# DIOT_CONN.net
KiCad netlist of a schematic drawn in Altium Designer
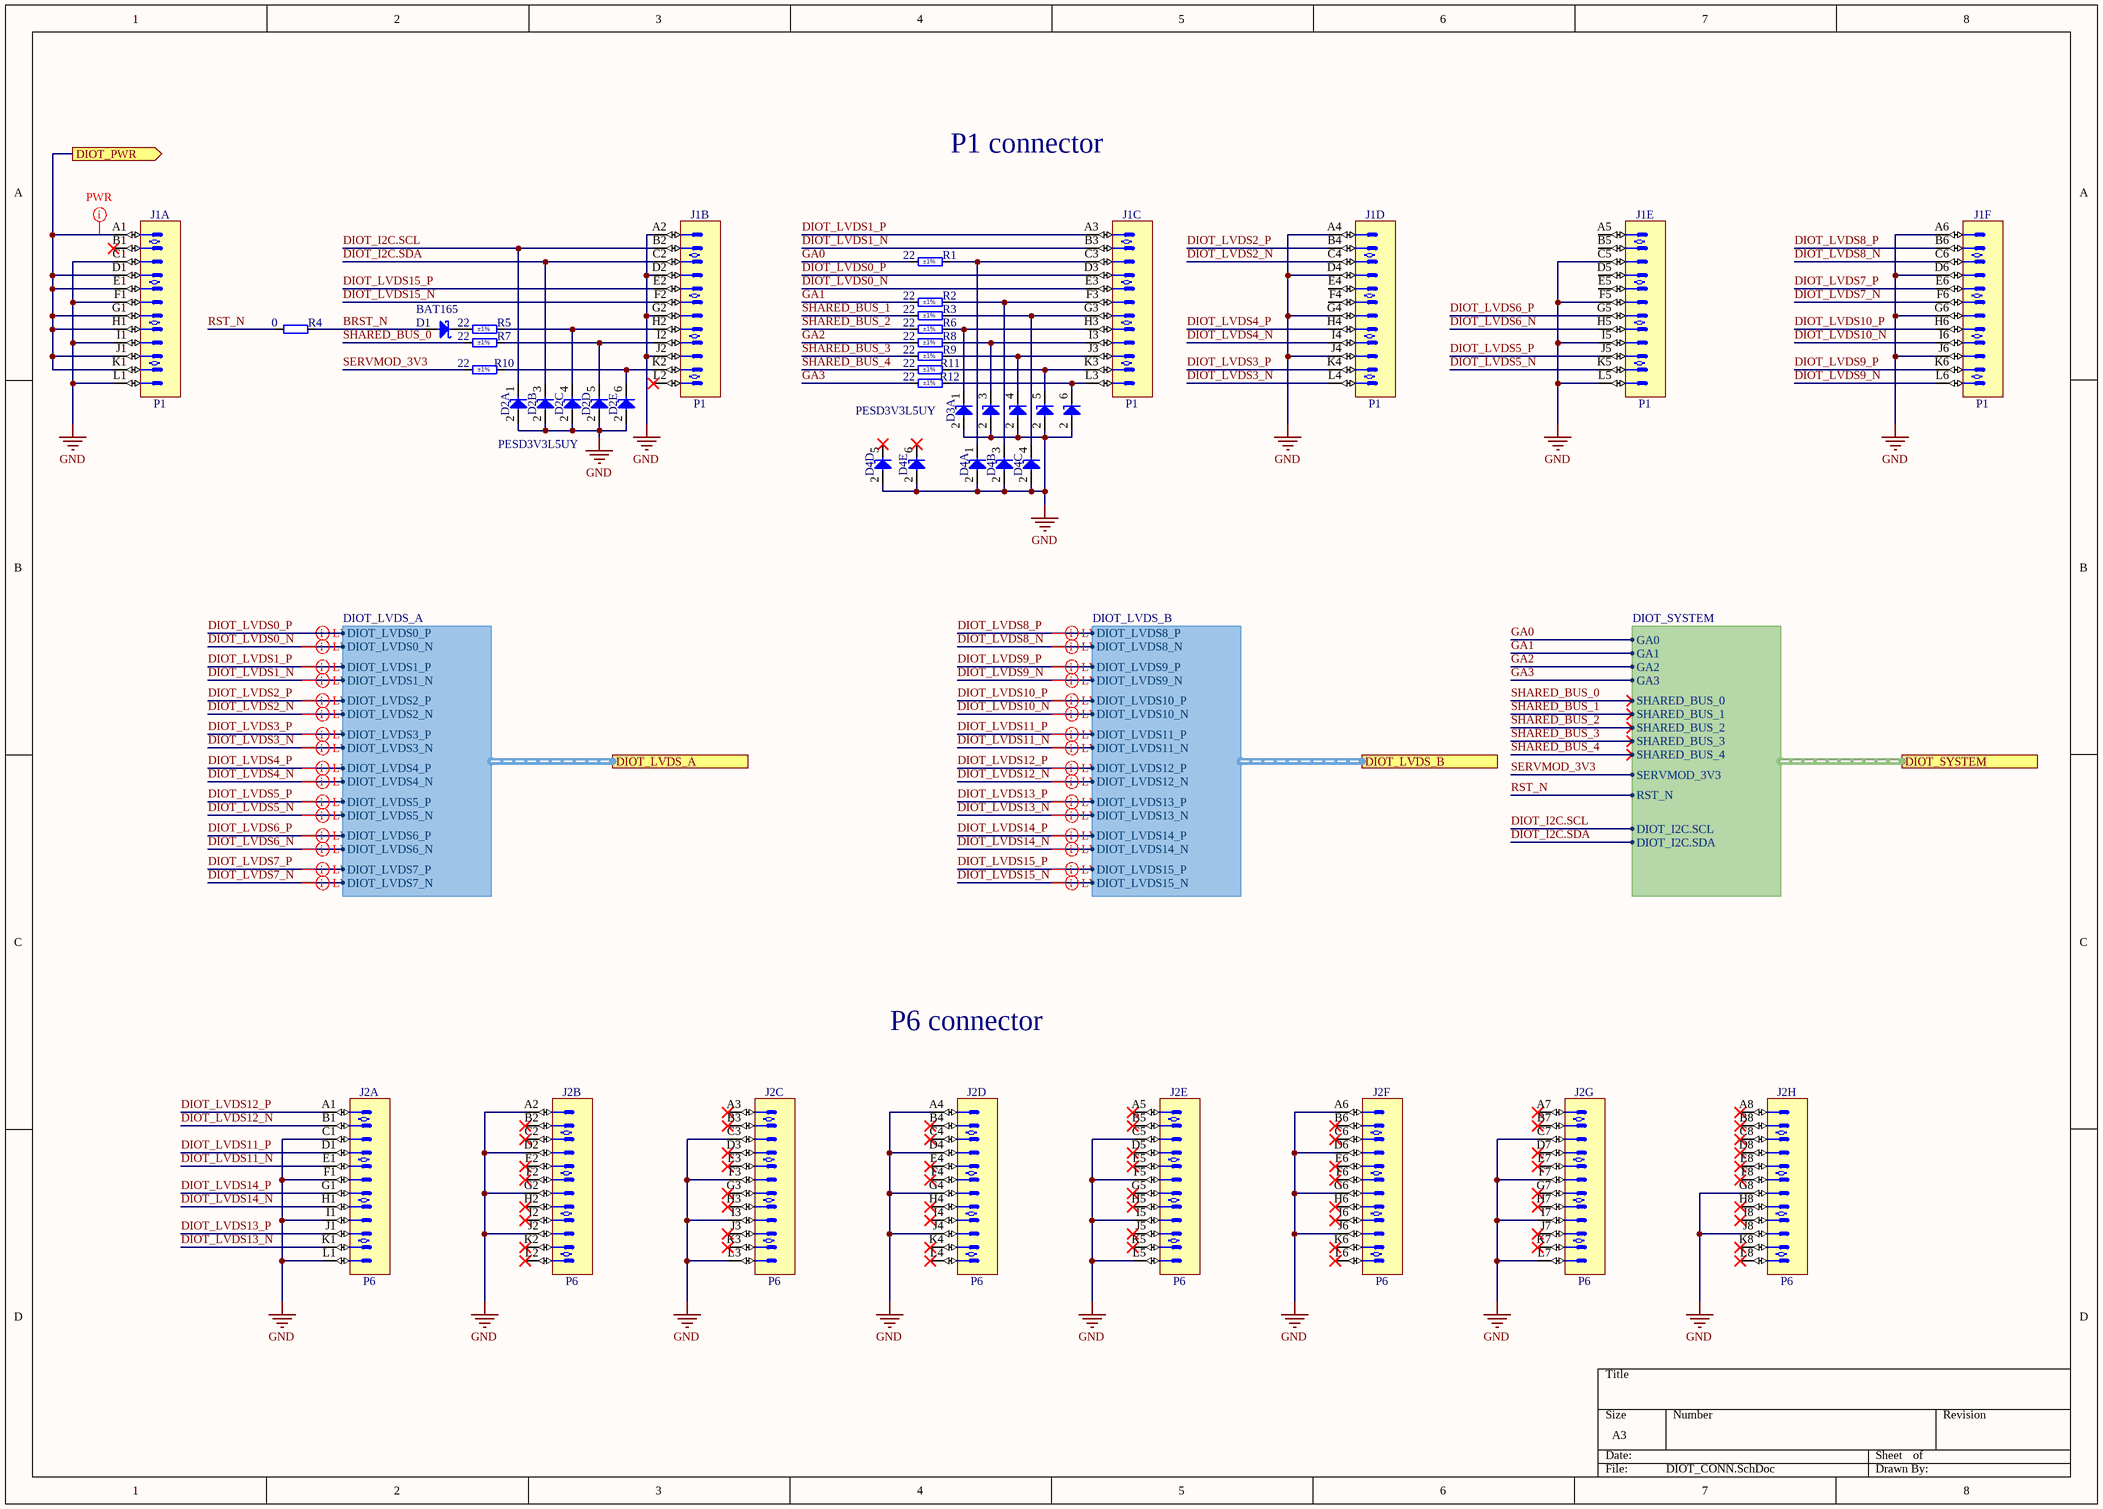
[diagram p0: DIOT_CONN.SchDoc]

(export (version "E")
  (design (tool "Eeschema 10.0.6"))
  (components
    (comp (ref "D1")
      (value "BAT165")
      (footprint "SOD2512X110N")
      (description "Schottky Diode")
      (fields
        (field (name "VOLTAGE") "40V")
        (field (name "POWER") "750mA")
        (field (name "AUTHOR") "CERN DEM JLC")
      )
      (libsource (lib "ICs And Semiconductors") (part "Diode Schottky"))
    )
    (comp (ref "D2")
      (value "PESD3V3L5UY")
      (footprint "SOT65P210X110-6N")
      (description "Fivefold ESD Protection Diode Arrays")
      (fields
        (field (name "VOLTAGE") "3.3V")
        (field (name "POWER") "200W")
        (field (name "AUTHOR") "CERN DEM WB")
      )
      (libsource (lib "ICs And Semiconductors") (part "PESD Array 5diodes 6pins Common anode2"))
    )
    (comp (ref "D3")
      (value "PESD3V3L5UY")
      (footprint "SOT65P210X110-6N")
      (description "Fivefold ESD Protection Diode Arrays")
      (fields
        (field (name "VOLTAGE") "3.3V")
        (field (name "POWER") "200W")
        (field (name "AUTHOR") "CERN DEM WB")
      )
      (libsource (lib "ICs And Semiconductors") (part "PESD Array 5diodes 6pins Common anode2"))
    )
    (comp (ref "D4")
      (value "PESD3V3L5UY")
      (footprint "SOT65P210X110-6N")
      (description "Fivefold ESD Protection Diode Arrays")
      (fields
        (field (name "VOLTAGE") "3.3V")
        (field (name "POWER") "200W")
        (field (name "AUTHOR") "CERN DEM WB")
      )
      (libsource (lib "ICs And Semiconductors") (part "PESD Array 5diodes 6pins Common anode2"))
    )
    (comp (ref "J1")
      (value "P1")
      (footprint "AMPHENOL_10052825-101LF")
      (description "72 Contacts Header, 6 Columns, 4 Pairs per Column")
      (fields
        (field (name "PART NUMBER") "AMPHENOL_10052825-101LF")
        (field (name "MANUFACTURER") "AMPHENOL")
        (field (name "AUTHOR") "CERN DEM MR")
      )
      (libsource (lib "Connectors") (part "AMPHENOL_10052825-101LF"))
    )
    (comp (ref "J2")
      (value "P6")
      (footprint "AMPHENOL_10052838-101LF")
      (description "96 Contacts Header, 8 Columns, 4 Pairs per Column")
      (fields
        (field (name "PART NUMBER") "AMPHENOL_10052838-101LF")
        (field (name "MANUFACTURER") "AMPHENOL")
        (field (name "AUTHOR") "CERN DEM MR")
      )
      (libsource (lib "Connectors") (part "AMPHENOL_10052838-101LF"))
    )
    (comp (ref "R1")
      (value "22")
      (footprint "RESC1005X40N")
      (description "Resistor - 1%")
      (fields
        (field (name "TOLERANCE") "±1%")
        (field (name "PART NUMBER") "R0402_22R_1%_0.0625W_100PPM")
        (field (name "POWER") "0.0625W")
        (field (name "AUTHOR") "CERN DEM JLC")
      )
      (libsource (lib "Resistors") (part "Resistor - 1%"))
    )
    (comp (ref "R2")
      (value "22")
      (footprint "RESC1005X40N")
      (description "Resistor - 1%")
      (fields
        (field (name "TOLERANCE") "±1%")
        (field (name "PART NUMBER") "R0402_22R_1%_0.0625W_100PPM")
        (field (name "POWER") "0.0625W")
        (field (name "AUTHOR") "CERN DEM JLC")
      )
      (libsource (lib "Resistors") (part "Resistor - 1%"))
    )
    (comp (ref "R3")
      (value "22")
      (footprint "RESC1005X40N")
      (description "Resistor - 1%")
      (fields
        (field (name "TOLERANCE") "±1%")
        (field (name "PART NUMBER") "R0402_22R_1%_0.0625W_100PPM")
        (field (name "POWER") "0.0625W")
        (field (name "AUTHOR") "CERN DEM JLC")
      )
      (libsource (lib "Resistors") (part "Resistor - 1%"))
    )
    (comp (ref "R4")
      (value "0")
      (footprint "RESC1005X40N")
      (description "Resistor")
      (fields
        (field (name "PART NUMBER") "R0402_0R_JUMPER")
        (field (name "MANUFACTURER") "GENERIC")
        (field (name "AUTHOR") "CERN DEM JLC")
      )
      (libsource (lib "Resistors") (part "Resistor"))
    )
    (comp (ref "R5")
      (value "22")
      (footprint "RESC1005X40N")
      (description "Resistor - 1%")
      (fields
        (field (name "TOLERANCE") "±1%")
        (field (name "PART NUMBER") "R0402_22R_1%_0.0625W_100PPM")
        (field (name "POWER") "0.0625W")
        (field (name "AUTHOR") "CERN DEM JLC")
      )
      (libsource (lib "Resistors") (part "Resistor - 1%"))
    )
    (comp (ref "R6")
      (value "22")
      (footprint "RESC1005X40N")
      (description "Resistor - 1%")
      (fields
        (field (name "TOLERANCE") "±1%")
        (field (name "PART NUMBER") "R0402_22R_1%_0.0625W_100PPM")
        (field (name "POWER") "0.0625W")
        (field (name "AUTHOR") "CERN DEM JLC")
      )
      (libsource (lib "Resistors") (part "Resistor - 1%"))
    )
    (comp (ref "R7")
      (value "22")
      (footprint "RESC1005X40N")
      (description "Resistor - 1%")
      (fields
        (field (name "TOLERANCE") "±1%")
        (field (name "PART NUMBER") "R0402_22R_1%_0.0625W_100PPM")
        (field (name "POWER") "0.0625W")
        (field (name "AUTHOR") "CERN DEM JLC")
      )
      (libsource (lib "Resistors") (part "Resistor - 1%"))
    )
    (comp (ref "R8")
      (value "22")
      (footprint "RESC1005X40N")
      (description "Resistor - 1%")
      (fields
        (field (name "TOLERANCE") "±1%")
        (field (name "PART NUMBER") "R0402_22R_1%_0.0625W_100PPM")
        (field (name "POWER") "0.0625W")
        (field (name "AUTHOR") "CERN DEM JLC")
      )
      (libsource (lib "Resistors") (part "Resistor - 1%"))
    )
    (comp (ref "R9")
      (value "22")
      (footprint "RESC1005X40N")
      (description "Resistor - 1%")
      (fields
        (field (name "TOLERANCE") "±1%")
        (field (name "PART NUMBER") "R0402_22R_1%_0.0625W_100PPM")
        (field (name "POWER") "0.0625W")
        (field (name "AUTHOR") "CERN DEM JLC")
      )
      (libsource (lib "Resistors") (part "Resistor - 1%"))
    )
    (comp (ref "R10")
      (value "22")
      (footprint "RESC1005X40N")
      (description "Resistor - 1%")
      (fields
        (field (name "TOLERANCE") "±1%")
        (field (name "PART NUMBER") "R0402_22R_1%_0.0625W_100PPM")
        (field (name "POWER") "0.0625W")
        (field (name "AUTHOR") "CERN DEM JLC")
      )
      (libsource (lib "Resistors") (part "Resistor - 1%"))
    )
    (comp (ref "R11")
      (value "22")
      (footprint "RESC1005X40N")
      (description "Resistor - 1%")
      (fields
        (field (name "TOLERANCE") "±1%")
        (field (name "PART NUMBER") "R0402_22R_1%_0.0625W_100PPM")
        (field (name "POWER") "0.0625W")
        (field (name "AUTHOR") "CERN DEM JLC")
      )
      (libsource (lib "Resistors") (part "Resistor - 1%"))
    )
    (comp (ref "R12")
      (value "22")
      (footprint "RESC1005X40N")
      (description "Resistor - 1%")
      (fields
        (field (name "TOLERANCE") "±1%")
        (field (name "PART NUMBER") "R0402_22R_1%_0.0625W_100PPM")
        (field (name "POWER") "0.0625W")
        (field (name "AUTHOR") "CERN DEM JLC")
      )
      (libsource (lib "Resistors") (part "Resistor - 1%"))
    )
  )
  (nets
    (net (code "4") (name "/BRST_N") (class "Default")
      (node (ref "D1") (pin "2") (pinfunction "A_2") (pintype "passive"))
      (node (ref "R4") (pin "2") (pinfunction "2_2") (pintype "passive"))
    )
    (net (code "5") (name "/DIOT_I2C.SCL") (class "Default")
      (node (ref "D2") (pin "1") (pinfunction "C_1") (pintype "passive"))
      (node (ref "J1") (pin "B2") (pinfunction "B2_B2") (pintype "bidirectional"))
    )
    (net (code "6") (name "/DIOT_I2C.SDA") (class "Default")
      (node (ref "D2") (pin "3") (pinfunction "C_3") (pintype "passive"))
      (node (ref "J1") (pin "C2") (pinfunction "C2_C2") (pintype "bidirectional"))
    )
    (net (code "7") (name "/DIOT_LVDS0_N") (class "Default")
      (node (ref "J1") (pin "E3") (pinfunction "E3_E3") (pintype "bidirectional"))
    )
    (net (code "8") (name "/DIOT_LVDS0_P") (class "Default")
      (node (ref "J1") (pin "D3") (pinfunction "D3_D3") (pintype "bidirectional"))
    )
    (net (code "9") (name "/DIOT_LVDS1_N") (class "Default")
      (node (ref "J1") (pin "B3") (pinfunction "B3_B3") (pintype "bidirectional"))
    )
    (net (code "10") (name "/DIOT_LVDS1_P") (class "Default")
      (node (ref "J1") (pin "A3") (pinfunction "A3_A3") (pintype "bidirectional"))
    )
    (net (code "11") (name "/DIOT_LVDS2_N") (class "Default")
      (node (ref "J1") (pin "C4") (pinfunction "C4_C4") (pintype "bidirectional"))
    )
    (net (code "12") (name "/DIOT_LVDS2_P") (class "Default")
      (node (ref "J1") (pin "B4") (pinfunction "B4_B4") (pintype "bidirectional"))
    )
    (net (code "13") (name "/DIOT_LVDS3_N") (class "Default")
      (node (ref "J1") (pin "L4") (pinfunction "L4_L4") (pintype "bidirectional"))
    )
    (net (code "14") (name "/DIOT_LVDS3_P") (class "Default")
      (node (ref "J1") (pin "K4") (pinfunction "K4_K4") (pintype "bidirectional"))
    )
    (net (code "15") (name "/DIOT_LVDS4_N") (class "Default")
      (node (ref "J1") (pin "I4") (pinfunction "I4_I4") (pintype "bidirectional"))
    )
    (net (code "16") (name "/DIOT_LVDS4_P") (class "Default")
      (node (ref "J1") (pin "H4") (pinfunction "H4_H4") (pintype "bidirectional"))
    )
    (net (code "17") (name "/DIOT_LVDS5_N") (class "Default")
      (node (ref "J1") (pin "K5") (pinfunction "K5_K5") (pintype "bidirectional"))
    )
    (net (code "18") (name "/DIOT_LVDS5_P") (class "Default")
      (node (ref "J1") (pin "J5") (pinfunction "J5_J5") (pintype "bidirectional"))
    )
    (net (code "19") (name "/DIOT_LVDS6_N") (class "Default")
      (node (ref "J1") (pin "H5") (pinfunction "H5_H5") (pintype "bidirectional"))
    )
    (net (code "20") (name "/DIOT_LVDS6_P") (class "Default")
      (node (ref "J1") (pin "G5") (pinfunction "G5_G5") (pintype "bidirectional"))
    )
    (net (code "21") (name "/DIOT_LVDS7_N") (class "Default")
      (node (ref "J1") (pin "F6") (pinfunction "F6_F6") (pintype "bidirectional"))
    )
    (net (code "22") (name "/DIOT_LVDS7_P") (class "Default")
      (node (ref "J1") (pin "E6") (pinfunction "E6_E6") (pintype "bidirectional"))
    )
    (net (code "23") (name "/DIOT_LVDS8_N") (class "Default")
      (node (ref "J1") (pin "C6") (pinfunction "C6_C6") (pintype "bidirectional"))
    )
    (net (code "24") (name "/DIOT_LVDS8_P") (class "Default")
      (node (ref "J1") (pin "B6") (pinfunction "B6_B6") (pintype "bidirectional"))
    )
    (net (code "25") (name "/DIOT_LVDS9_N") (class "Default")
      (node (ref "J1") (pin "L6") (pinfunction "L6_L6") (pintype "bidirectional"))
    )
    (net (code "26") (name "/DIOT_LVDS9_P") (class "Default")
      (node (ref "J1") (pin "K6") (pinfunction "K6_K6") (pintype "bidirectional"))
    )
    (net (code "27") (name "/DIOT_LVDS10_N") (class "Default")
      (node (ref "J1") (pin "I6") (pinfunction "I6_I6") (pintype "bidirectional"))
    )
    (net (code "28") (name "/DIOT_LVDS10_P") (class "Default")
      (node (ref "J1") (pin "H6") (pinfunction "H6_H6") (pintype "bidirectional"))
    )
    (net (code "29") (name "/DIOT_LVDS11_N") (class "Default")
      (node (ref "J2") (pin "E1") (pinfunction "E1_E1") (pintype "bidirectional"))
    )
    (net (code "30") (name "/DIOT_LVDS11_P") (class "Default")
      (node (ref "J2") (pin "D1") (pinfunction "D1_D1") (pintype "bidirectional"))
    )
    (net (code "31") (name "/DIOT_LVDS12_N") (class "Default")
      (node (ref "J2") (pin "B1") (pinfunction "B1_B1") (pintype "bidirectional"))
    )
    (net (code "32") (name "/DIOT_LVDS12_P") (class "Default")
      (node (ref "J2") (pin "A1") (pinfunction "A1_A1") (pintype "bidirectional"))
    )
    (net (code "33") (name "/DIOT_LVDS13_N") (class "Default")
      (node (ref "J2") (pin "K1") (pinfunction "K1_K1") (pintype "bidirectional"))
    )
    (net (code "34") (name "/DIOT_LVDS13_P") (class "Default")
      (node (ref "J2") (pin "J1") (pinfunction "J1_J1") (pintype "bidirectional"))
    )
    (net (code "35") (name "/DIOT_LVDS14_N") (class "Default")
      (node (ref "J2") (pin "H1") (pinfunction "H1_H1") (pintype "bidirectional"))
    )
    (net (code "36") (name "/DIOT_LVDS14_P") (class "Default")
      (node (ref "J2") (pin "G1") (pinfunction "G1_G1") (pintype "bidirectional"))
    )
    (net (code "37") (name "/DIOT_LVDS15_N") (class "Default")
      (node (ref "J1") (pin "F2") (pinfunction "F2_F2") (pintype "bidirectional"))
    )
    (net (code "38") (name "/DIOT_LVDS15_P") (class "Default")
      (node (ref "J1") (pin "E2") (pinfunction "E2_E2") (pintype "bidirectional"))
    )
    (net (code "39") (name "/DIOT_PWR") (class "Default")
      (node (ref "J1") (pin "A1") (pinfunction "A1_A1") (pintype "bidirectional"))
      (node (ref "J1") (pin "D1") (pinfunction "D1_D1") (pintype "bidirectional"))
      (node (ref "J1") (pin "E1") (pinfunction "E1_E1") (pintype "bidirectional"))
      (node (ref "J1") (pin "G1") (pinfunction "G1_G1") (pintype "bidirectional"))
      (node (ref "J1") (pin "H1") (pinfunction "H1_H1") (pintype "bidirectional"))
      (node (ref "J1") (pin "J1") (pinfunction "J1_J1") (pintype "bidirectional"))
      (node (ref "J1") (pin "K1") (pinfunction "K1_K1") (pintype "bidirectional"))
    )
    (net (code "40") (name "/GA0") (class "Default")
      (node (ref "R1") (pin "1") (pinfunction "1_1") (pintype "passive"))
    )
    (net (code "41") (name "/GA1") (class "Default")
      (node (ref "R2") (pin "1") (pinfunction "1_1") (pintype "passive"))
    )
    (net (code "42") (name "/GA2") (class "Default")
      (node (ref "R8") (pin "1") (pinfunction "1_1") (pintype "passive"))
    )
    (net (code "43") (name "/GA3") (class "Default")
      (node (ref "R12") (pin "1") (pinfunction "1_1") (pintype "passive"))
    )
    (net (code "44") (name "/RST_N") (class "Default")
      (node (ref "R4") (pin "1") (pinfunction "1_1") (pintype "passive"))
    )
    (net (code "45") (name "/SERVMOD_3V3") (class "Default")
      (node (ref "R10") (pin "1") (pinfunction "1_1") (pintype "passive"))
    )
    (net (code "46") (name "/SHARED_BUS_0") (class "Default")
      (node (ref "R7") (pin "1") (pinfunction "1_1") (pintype "passive+no_connect"))
    )
    (net (code "47") (name "/SHARED_BUS_1") (class "Default")
      (node (ref "R3") (pin "1") (pinfunction "1_1") (pintype "passive+no_connect"))
    )
    (net (code "48") (name "/SHARED_BUS_2") (class "Default")
      (node (ref "R6") (pin "1") (pinfunction "1_1") (pintype "passive+no_connect"))
    )
    (net (code "49") (name "/SHARED_BUS_3") (class "Default")
      (node (ref "R9") (pin "1") (pinfunction "1_1") (pintype "passive+no_connect"))
    )
    (net (code "50") (name "/SHARED_BUS_4") (class "Default")
      (node (ref "R11") (pin "1") (pinfunction "1_1") (pintype "passive+no_connect"))
    )
    (net (code "54") (name "GND") (class "Default")
      (node (ref "D2") (pin "2") (pinfunction "A_2") (pintype "passive"))
      (node (ref "D3") (pin "2") (pinfunction "A_2") (pintype "passive"))
      (node (ref "D4") (pin "2") (pinfunction "A_2") (pintype "passive"))
      (node (ref "J1") (pin "A2") (pinfunction "A2_A2") (pintype "bidirectional"))
      (node (ref "J1") (pin "A4") (pinfunction "A4_A4") (pintype "bidirectional"))
      (node (ref "J1") (pin "A6") (pinfunction "A6_A6") (pintype "bidirectional"))
      (node (ref "J1") (pin "C1") (pinfunction "C1_C1") (pintype "bidirectional"))
      (node (ref "J1") (pin "C5") (pinfunction "C5_C5") (pintype "bidirectional"))
      (node (ref "J1") (pin "D2") (pinfunction "D2_D2") (pintype "bidirectional"))
      (node (ref "J1") (pin "D4") (pinfunction "D4_D4") (pintype "bidirectional"))
      (node (ref "J1") (pin "D6") (pinfunction "D6_D6") (pintype "bidirectional"))
      (node (ref "J1") (pin "F1") (pinfunction "F1_F1") (pintype "bidirectional"))
      (node (ref "J1") (pin "F5") (pinfunction "F5_F5") (pintype "bidirectional"))
      (node (ref "J1") (pin "G2") (pinfunction "G2_G2") (pintype "bidirectional"))
      (node (ref "J1") (pin "G4") (pinfunction "G4_G4") (pintype "bidirectional"))
      (node (ref "J1") (pin "G6") (pinfunction "G6_G6") (pintype "bidirectional"))
      (node (ref "J1") (pin "I1") (pinfunction "I1_I1") (pintype "bidirectional"))
      (node (ref "J1") (pin "I5") (pinfunction "I5_I5") (pintype "bidirectional"))
      (node (ref "J1") (pin "J2") (pinfunction "J2_J2") (pintype "bidirectional"))
      (node (ref "J1") (pin "J4") (pinfunction "J4_J4") (pintype "bidirectional"))
      (node (ref "J1") (pin "J6") (pinfunction "J6_J6") (pintype "bidirectional"))
      (node (ref "J1") (pin "L1") (pinfunction "L1_L1") (pintype "bidirectional"))
      (node (ref "J1") (pin "L5") (pinfunction "L5_L5") (pintype "bidirectional"))
      (node (ref "J2") (pin "A2") (pinfunction "A2_A2") (pintype "bidirectional"))
      (node (ref "J2") (pin "A4") (pinfunction "A4_A4") (pintype "bidirectional"))
      (node (ref "J2") (pin "A6") (pinfunction "A6_A6") (pintype "bidirectional"))
      (node (ref "J2") (pin "C1") (pinfunction "C1_C1") (pintype "bidirectional"))
      (node (ref "J2") (pin "C3") (pinfunction "C3_C3") (pintype "bidirectional"))
      (node (ref "J2") (pin "C5") (pinfunction "C5_C5") (pintype "bidirectional"))
      (node (ref "J2") (pin "C7") (pinfunction "C7_C7") (pintype "bidirectional"))
      (node (ref "J2") (pin "D2") (pinfunction "D2_D2") (pintype "bidirectional"))
      (node (ref "J2") (pin "D4") (pinfunction "D4_D4") (pintype "bidirectional"))
      (node (ref "J2") (pin "D6") (pinfunction "D6_D6") (pintype "bidirectional"))
      (node (ref "J2") (pin "F1") (pinfunction "F1_F1") (pintype "bidirectional"))
      (node (ref "J2") (pin "F3") (pinfunction "F3_F3") (pintype "bidirectional"))
      (node (ref "J2") (pin "F5") (pinfunction "F5_F5") (pintype "bidirectional"))
      (node (ref "J2") (pin "F7") (pinfunction "F7_F7") (pintype "bidirectional"))
      (node (ref "J2") (pin "G2") (pinfunction "G2_G2") (pintype "bidirectional"))
      (node (ref "J2") (pin "G4") (pinfunction "G4_G4") (pintype "bidirectional"))
      (node (ref "J2") (pin "G6") (pinfunction "G6_G6") (pintype "bidirectional"))
      (node (ref "J2") (pin "G8") (pinfunction "G8_G8") (pintype "bidirectional"))
      (node (ref "J2") (pin "I1") (pinfunction "I1_I1") (pintype "bidirectional"))
      (node (ref "J2") (pin "I3") (pinfunction "I3_I3") (pintype "bidirectional"))
      (node (ref "J2") (pin "I5") (pinfunction "I5_I5") (pintype "bidirectional"))
      (node (ref "J2") (pin "I7") (pinfunction "I7_I7") (pintype "bidirectional"))
      (node (ref "J2") (pin "J2") (pinfunction "J2_J2") (pintype "bidirectional"))
      (node (ref "J2") (pin "J4") (pinfunction "J4_J4") (pintype "bidirectional"))
      (node (ref "J2") (pin "J6") (pinfunction "J6_J6") (pintype "bidirectional"))
      (node (ref "J2") (pin "J8") (pinfunction "J8_J8") (pintype "bidirectional"))
      (node (ref "J2") (pin "L1") (pinfunction "L1_L1") (pintype "bidirectional"))
      (node (ref "J2") (pin "L3") (pinfunction "L3_L3") (pintype "bidirectional"))
      (node (ref "J2") (pin "L5") (pinfunction "L5_L5") (pintype "bidirectional"))
      (node (ref "J2") (pin "L7") (pinfunction "L7_L7") (pintype "bidirectional"))
    )
    (net (code "55") (name "Net-(D1-C)") (class "Default")
      (node (ref "D1") (pin "1") (pinfunction "C_1") (pintype "passive"))
      (node (ref "R5") (pin "1") (pinfunction "1_1") (pintype "passive"))
    )
    (net (code "56") (name "Net-(D2C-C)") (class "Default")
      (node (ref "D2") (pin "4") (pinfunction "C_4") (pintype "passive"))
      (node (ref "J1") (pin "H2") (pinfunction "H2_H2") (pintype "bidirectional"))
      (node (ref "R5") (pin "2") (pinfunction "2_2") (pintype "passive"))
    )
    (net (code "57") (name "Net-(D2D-C)") (class "Default")
      (node (ref "D2") (pin "5") (pinfunction "C_5") (pintype "passive"))
      (node (ref "J1") (pin "I2") (pinfunction "I2_I2") (pintype "bidirectional"))
      (node (ref "R7") (pin "2") (pinfunction "2_2") (pintype "passive"))
    )
    (net (code "58") (name "Net-(D2E-C)") (class "Default")
      (node (ref "D2") (pin "6") (pinfunction "C_6") (pintype "passive"))
      (node (ref "J1") (pin "K2") (pinfunction "K2_K2") (pintype "bidirectional"))
      (node (ref "R10") (pin "2") (pinfunction "2_2") (pintype "passive"))
    )
    (net (code "59") (name "Net-(D3A-C)") (class "Default")
      (node (ref "D3") (pin "1") (pinfunction "C_1") (pintype "passive"))
      (node (ref "J1") (pin "H3") (pinfunction "H3_H3") (pintype "bidirectional"))
      (node (ref "R6") (pin "2") (pinfunction "2_2") (pintype "passive"))
    )
    (net (code "60") (name "Net-(D3B-C)") (class "Default")
      (node (ref "D3") (pin "3") (pinfunction "C_3") (pintype "passive"))
      (node (ref "J1") (pin "I3") (pinfunction "I3_I3") (pintype "bidirectional"))
      (node (ref "R8") (pin "2") (pinfunction "2_2") (pintype "passive"))
    )
    (net (code "61") (name "Net-(D3C-C)") (class "Default")
      (node (ref "D3") (pin "4") (pinfunction "C_4") (pintype "passive"))
      (node (ref "J1") (pin "J3") (pinfunction "J3_J3") (pintype "bidirectional"))
      (node (ref "R9") (pin "2") (pinfunction "2_2") (pintype "passive"))
    )
    (net (code "62") (name "Net-(D3D-C)") (class "Default")
      (node (ref "D3") (pin "5") (pinfunction "C_5") (pintype "passive"))
      (node (ref "J1") (pin "K3") (pinfunction "K3_K3") (pintype "bidirectional"))
      (node (ref "R11") (pin "2") (pinfunction "2_2") (pintype "passive"))
    )
    (net (code "63") (name "Net-(D3E-C)") (class "Default")
      (node (ref "D3") (pin "6") (pinfunction "C_6") (pintype "passive"))
      (node (ref "J1") (pin "L3") (pinfunction "L3_L3") (pintype "bidirectional"))
      (node (ref "R12") (pin "2") (pinfunction "2_2") (pintype "passive"))
    )
    (net (code "64") (name "Net-(D4A-C)") (class "Default")
      (node (ref "D4") (pin "1") (pinfunction "C_1") (pintype "passive"))
      (node (ref "J1") (pin "C3") (pinfunction "C3_C3") (pintype "bidirectional"))
      (node (ref "R1") (pin "2") (pinfunction "2_2") (pintype "passive"))
    )
    (net (code "65") (name "Net-(D4B-C)") (class "Default")
      (node (ref "D4") (pin "3") (pinfunction "C_3") (pintype "passive"))
      (node (ref "J1") (pin "F3") (pinfunction "F3_F3") (pintype "bidirectional"))
      (node (ref "R2") (pin "2") (pinfunction "2_2") (pintype "passive"))
    )
    (net (code "66") (name "Net-(D4C-C)") (class "Default")
      (node (ref "D4") (pin "4") (pinfunction "C_4") (pintype "passive"))
      (node (ref "J1") (pin "G3") (pinfunction "G3_G3") (pintype "bidirectional"))
      (node (ref "R3") (pin "2") (pinfunction "2_2") (pintype "passive"))
    )
    (net (code "67") (name "unconnected-(D4D-C-Pad5)") (class "Default")
      (node (ref "D4") (pin "5") (pinfunction "C_5") (pintype "passive+no_connect"))
    )
    (net (code "68") (name "unconnected-(D4E-C-Pad6)") (class "Default")
      (node (ref "D4") (pin "6") (pinfunction "C_6") (pintype "passive+no_connect"))
    )
    (net (code "69") (name "unconnected-(J1-PadA5)") (class "Default")
      (node (ref "J1") (pin "A5") (pinfunction "A5_A5") (pintype "bidirectional"))
    )
    (net (code "70") (name "unconnected-(J1-PadB1)") (class "Default")
      (node (ref "J1") (pin "B1") (pinfunction "B1_B1") (pintype "bidirectional+no_connect"))
    )
    (net (code "71") (name "unconnected-(J1-PadB5)") (class "Default")
      (node (ref "J1") (pin "B5") (pinfunction "B5_B5") (pintype "bidirectional"))
    )
    (net (code "72") (name "unconnected-(J1-PadD5)") (class "Default")
      (node (ref "J1") (pin "D5") (pinfunction "D5_D5") (pintype "bidirectional"))
    )
    (net (code "73") (name "unconnected-(J1-PadE4)") (class "Default")
      (node (ref "J1") (pin "E4") (pinfunction "E4_E4") (pintype "bidirectional"))
    )
    (net (code "74") (name "unconnected-(J1-PadE5)") (class "Default")
      (node (ref "J1") (pin "E5") (pinfunction "E5_E5") (pintype "bidirectional"))
    )
    (net (code "75") (name "unconnected-(J1-PadF4)") (class "Default")
      (node (ref "J1") (pin "F4") (pinfunction "F4_F4") (pintype "bidirectional"))
    )
    (net (code "76") (name "unconnected-(J1-PadL2)") (class "Default")
      (node (ref "J1") (pin "L2") (pinfunction "L2_L2") (pintype "bidirectional+no_connect"))
    )
    (net (code "77") (name "unconnected-(J2-PadA3)") (class "Default")
      (node (ref "J2") (pin "A3") (pinfunction "A3_A3") (pintype "bidirectional+no_connect"))
    )
    (net (code "78") (name "unconnected-(J2-PadA5)") (class "Default")
      (node (ref "J2") (pin "A5") (pinfunction "A5_A5") (pintype "bidirectional+no_connect"))
    )
    (net (code "79") (name "unconnected-(J2-PadA7)") (class "Default")
      (node (ref "J2") (pin "A7") (pinfunction "A7_A7") (pintype "bidirectional+no_connect"))
    )
    (net (code "80") (name "unconnected-(J2-PadA8)") (class "Default")
      (node (ref "J2") (pin "A8") (pinfunction "A8_A8") (pintype "bidirectional+no_connect"))
    )
    (net (code "81") (name "unconnected-(J2-PadB2)") (class "Default")
      (node (ref "J2") (pin "B2") (pinfunction "B2_B2") (pintype "bidirectional+no_connect"))
    )
    (net (code "82") (name "unconnected-(J2-PadB3)") (class "Default")
      (node (ref "J2") (pin "B3") (pinfunction "B3_B3") (pintype "bidirectional+no_connect"))
    )
    (net (code "83") (name "unconnected-(J2-PadB4)") (class "Default")
      (node (ref "J2") (pin "B4") (pinfunction "B4_B4") (pintype "bidirectional+no_connect"))
    )
    (net (code "84") (name "unconnected-(J2-PadB5)") (class "Default")
      (node (ref "J2") (pin "B5") (pinfunction "B5_B5") (pintype "bidirectional+no_connect"))
    )
    (net (code "85") (name "unconnected-(J2-PadB6)") (class "Default")
      (node (ref "J2") (pin "B6") (pinfunction "B6_B6") (pintype "bidirectional+no_connect"))
    )
    (net (code "86") (name "unconnected-(J2-PadB7)") (class "Default")
      (node (ref "J2") (pin "B7") (pinfunction "B7_B7") (pintype "bidirectional+no_connect"))
    )
    (net (code "87") (name "unconnected-(J2-PadB8)") (class "Default")
      (node (ref "J2") (pin "B8") (pinfunction "B8_B8") (pintype "bidirectional+no_connect"))
    )
    (net (code "88") (name "unconnected-(J2-PadC2)") (class "Default")
      (node (ref "J2") (pin "C2") (pinfunction "C2_C2") (pintype "bidirectional+no_connect"))
    )
    (net (code "89") (name "unconnected-(J2-PadC4)") (class "Default")
      (node (ref "J2") (pin "C4") (pinfunction "C4_C4") (pintype "bidirectional+no_connect"))
    )
    (net (code "90") (name "unconnected-(J2-PadC6)") (class "Default")
      (node (ref "J2") (pin "C6") (pinfunction "C6_C6") (pintype "bidirectional+no_connect"))
    )
    (net (code "91") (name "unconnected-(J2-PadC8)") (class "Default")
      (node (ref "J2") (pin "C8") (pinfunction "C8_C8") (pintype "bidirectional+no_connect"))
    )
    (net (code "92") (name "unconnected-(J2-PadD3)") (class "Default")
      (node (ref "J2") (pin "D3") (pinfunction "D3_D3") (pintype "bidirectional+no_connect"))
    )
    (net (code "93") (name "unconnected-(J2-PadD5)") (class "Default")
      (node (ref "J2") (pin "D5") (pinfunction "D5_D5") (pintype "bidirectional+no_connect"))
    )
    (net (code "94") (name "unconnected-(J2-PadD7)") (class "Default")
      (node (ref "J2") (pin "D7") (pinfunction "D7_D7") (pintype "bidirectional+no_connect"))
    )
    (net (code "95") (name "unconnected-(J2-PadD8)") (class "Default")
      (node (ref "J2") (pin "D8") (pinfunction "D8_D8") (pintype "bidirectional+no_connect"))
    )
    (net (code "96") (name "unconnected-(J2-PadE2)") (class "Default")
      (node (ref "J2") (pin "E2") (pinfunction "E2_E2") (pintype "bidirectional+no_connect"))
    )
    (net (code "97") (name "unconnected-(J2-PadE3)") (class "Default")
      (node (ref "J2") (pin "E3") (pinfunction "E3_E3") (pintype "bidirectional+no_connect"))
    )
    (net (code "98") (name "unconnected-(J2-PadE4)") (class "Default")
      (node (ref "J2") (pin "E4") (pinfunction "E4_E4") (pintype "bidirectional+no_connect"))
    )
    (net (code "99") (name "unconnected-(J2-PadE5)") (class "Default")
      (node (ref "J2") (pin "E5") (pinfunction "E5_E5") (pintype "bidirectional+no_connect"))
    )
    (net (code "100") (name "unconnected-(J2-PadE6)") (class "Default")
      (node (ref "J2") (pin "E6") (pinfunction "E6_E6") (pintype "bidirectional+no_connect"))
    )
    (net (code "101") (name "unconnected-(J2-PadE7)") (class "Default")
      (node (ref "J2") (pin "E7") (pinfunction "E7_E7") (pintype "bidirectional+no_connect"))
    )
    (net (code "102") (name "unconnected-(J2-PadE8)") (class "Default")
      (node (ref "J2") (pin "E8") (pinfunction "E8_E8") (pintype "bidirectional+no_connect"))
    )
    (net (code "103") (name "unconnected-(J2-PadF2)") (class "Default")
      (node (ref "J2") (pin "F2") (pinfunction "F2_F2") (pintype "bidirectional+no_connect"))
    )
    (net (code "104") (name "unconnected-(J2-PadF4)") (class "Default")
      (node (ref "J2") (pin "F4") (pinfunction "F4_F4") (pintype "bidirectional+no_connect"))
    )
    (net (code "105") (name "unconnected-(J2-PadF6)") (class "Default")
      (node (ref "J2") (pin "F6") (pinfunction "F6_F6") (pintype "bidirectional+no_connect"))
    )
    (net (code "106") (name "unconnected-(J2-PadF8)") (class "Default")
      (node (ref "J2") (pin "F8") (pinfunction "F8_F8") (pintype "bidirectional+no_connect"))
    )
    (net (code "107") (name "unconnected-(J2-PadG3)") (class "Default")
      (node (ref "J2") (pin "G3") (pinfunction "G3_G3") (pintype "bidirectional+no_connect"))
    )
    (net (code "108") (name "unconnected-(J2-PadG5)") (class "Default")
      (node (ref "J2") (pin "G5") (pinfunction "G5_G5") (pintype "bidirectional+no_connect"))
    )
    (net (code "109") (name "unconnected-(J2-PadG7)") (class "Default")
      (node (ref "J2") (pin "G7") (pinfunction "G7_G7") (pintype "bidirectional+no_connect"))
    )
    (net (code "110") (name "unconnected-(J2-PadH2)") (class "Default")
      (node (ref "J2") (pin "H2") (pinfunction "H2_H2") (pintype "bidirectional+no_connect"))
    )
    (net (code "111") (name "unconnected-(J2-PadH3)") (class "Default")
      (node (ref "J2") (pin "H3") (pinfunction "H3_H3") (pintype "bidirectional+no_connect"))
    )
    (net (code "112") (name "unconnected-(J2-PadH4)") (class "Default")
      (node (ref "J2") (pin "H4") (pinfunction "H4_H4") (pintype "bidirectional+no_connect"))
    )
    (net (code "113") (name "unconnected-(J2-PadH5)") (class "Default")
      (node (ref "J2") (pin "H5") (pinfunction "H5_H5") (pintype "bidirectional+no_connect"))
    )
    (net (code "114") (name "unconnected-(J2-PadH6)") (class "Default")
      (node (ref "J2") (pin "H6") (pinfunction "H6_H6") (pintype "bidirectional+no_connect"))
    )
    (net (code "115") (name "unconnected-(J2-PadH7)") (class "Default")
      (node (ref "J2") (pin "H7") (pinfunction "H7_H7") (pintype "bidirectional+no_connect"))
    )
    (net (code "116") (name "unconnected-(J2-PadH8)") (class "Default")
      (node (ref "J2") (pin "H8") (pinfunction "H8_H8") (pintype "bidirectional+no_connect"))
    )
    (net (code "117") (name "unconnected-(J2-PadI2)") (class "Default")
      (node (ref "J2") (pin "I2") (pinfunction "I2_I2") (pintype "bidirectional+no_connect"))
    )
    (net (code "118") (name "unconnected-(J2-PadI4)") (class "Default")
      (node (ref "J2") (pin "I4") (pinfunction "I4_I4") (pintype "bidirectional+no_connect"))
    )
    (net (code "119") (name "unconnected-(J2-PadI6)") (class "Default")
      (node (ref "J2") (pin "I6") (pinfunction "I6_I6") (pintype "bidirectional+no_connect"))
    )
    (net (code "120") (name "unconnected-(J2-PadI8)") (class "Default")
      (node (ref "J2") (pin "I8") (pinfunction "I8_I8") (pintype "bidirectional+no_connect"))
    )
    (net (code "121") (name "unconnected-(J2-PadJ3)") (class "Default")
      (node (ref "J2") (pin "J3") (pinfunction "J3_J3") (pintype "bidirectional+no_connect"))
    )
    (net (code "122") (name "unconnected-(J2-PadJ5)") (class "Default")
      (node (ref "J2") (pin "J5") (pinfunction "J5_J5") (pintype "bidirectional+no_connect"))
    )
    (net (code "123") (name "unconnected-(J2-PadJ7)") (class "Default")
      (node (ref "J2") (pin "J7") (pinfunction "J7_J7") (pintype "bidirectional+no_connect"))
    )
    (net (code "124") (name "unconnected-(J2-PadK2)") (class "Default")
      (node (ref "J2") (pin "K2") (pinfunction "K2_K2") (pintype "bidirectional+no_connect"))
    )
    (net (code "125") (name "unconnected-(J2-PadK3)") (class "Default")
      (node (ref "J2") (pin "K3") (pinfunction "K3_K3") (pintype "bidirectional+no_connect"))
    )
    (net (code "126") (name "unconnected-(J2-PadK4)") (class "Default")
      (node (ref "J2") (pin "K4") (pinfunction "K4_K4") (pintype "bidirectional+no_connect"))
    )
    (net (code "127") (name "unconnected-(J2-PadK5)") (class "Default")
      (node (ref "J2") (pin "K5") (pinfunction "K5_K5") (pintype "bidirectional+no_connect"))
    )
    (net (code "128") (name "unconnected-(J2-PadK6)") (class "Default")
      (node (ref "J2") (pin "K6") (pinfunction "K6_K6") (pintype "bidirectional+no_connect"))
    )
    (net (code "129") (name "unconnected-(J2-PadK7)") (class "Default")
      (node (ref "J2") (pin "K7") (pinfunction "K7_K7") (pintype "bidirectional+no_connect"))
    )
    (net (code "130") (name "unconnected-(J2-PadK8)") (class "Default")
      (node (ref "J2") (pin "K8") (pinfunction "K8_K8") (pintype "bidirectional+no_connect"))
    )
    (net (code "131") (name "unconnected-(J2-PadL2)") (class "Default")
      (node (ref "J2") (pin "L2") (pinfunction "L2_L2") (pintype "bidirectional+no_connect"))
    )
    (net (code "132") (name "unconnected-(J2-PadL4)") (class "Default")
      (node (ref "J2") (pin "L4") (pinfunction "L4_L4") (pintype "bidirectional+no_connect"))
    )
    (net (code "133") (name "unconnected-(J2-PadL6)") (class "Default")
      (node (ref "J2") (pin "L6") (pinfunction "L6_L6") (pintype "bidirectional+no_connect"))
    )
    (net (code "134") (name "unconnected-(J2-PadL8)") (class "Default")
      (node (ref "J2") (pin "L8") (pinfunction "L8_L8") (pintype "bidirectional+no_connect"))
    )
  )
)
